# rolling_resistance.net
KiCad netlist of a schematic drawn in EAGLE
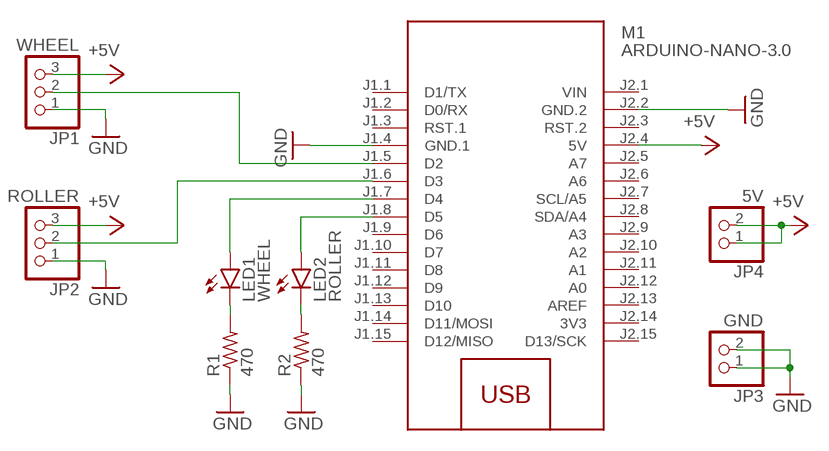
[diagram p0: schematic, sheet 1]

(export (version "E")
  (design (tool "Eeschema 10.0.6"))
  (components
    (comp (ref "JP1")
      (value "WHEEL")
      (footprint "eagle-import:1X03")
      (libsource (lib "eagle-import") (part "PINHD-1X3"))
    )
    (comp (ref "JP2")
      (value "ROLLER")
      (footprint "eagle-import:1X03")
      (libsource (lib "eagle-import") (part "PINHD-1X3"))
    )
    (comp (ref "JP3")
      (value "GND")
      (footprint "eagle-import:1X02")
      (libsource (lib "eagle-import") (part "PINHD-1X2"))
    )
    (comp (ref "JP4")
      (value "5V")
      (footprint "eagle-import:1X02")
      (libsource (lib "eagle-import") (part "PINHD-1X2"))
    )
    (comp (ref "LED1")
      (value "WHEEL")
      (footprint "eagle-import:SML0805")
      (libsource (lib "eagle-import") (part "LEDSML0805"))
    )
    (comp (ref "LED2")
      (value "ROLLER")
      (footprint "eagle-import:SML0805")
      (libsource (lib "eagle-import") (part "LEDSML0805"))
    )
    (comp (ref "M1")
      (value "ARDUINO-NANO-3.0")
      (footprint "eagle-import:ARDUINO-NANO-3.0")
      (libsource (lib "eagle-import") (part "ARDUINO-NANO-3.0"))
    )
    (comp (ref "R1")
      (value "470")
      (footprint "eagle-import:R0805")
      (libsource (lib "eagle-import") (part "R-US_R0805"))
    )
    (comp (ref "R2")
      (value "470")
      (footprint "eagle-import:R0805")
      (libsource (lib "eagle-import") (part "R-US_R0805"))
    )
  )
  (nets
    (net (code "1") (name "+5V") (class "Default")
      (node (ref "JP1") (pin "3") (pinfunction "3_3") (pintype "passive"))
      (node (ref "JP2") (pin "3") (pinfunction "3_3") (pintype "passive"))
      (node (ref "JP4") (pin "1") (pinfunction "1_1") (pintype "passive"))
      (node (ref "JP4") (pin "2") (pinfunction "2_2") (pintype "passive"))
      (node (ref "M1") (pin "J2.4") (pinfunction "5V_J2.4") (pintype "power_in"))
    )
    (net (code "2") (name "/3V3") (class "Default")
      (node (ref "M1") (pin "J2.14") (pinfunction "3V3_J2.14") (pintype "power_in"))
    )
    (net (code "3") (name "/VIN") (class "Default")
      (node (ref "M1") (pin "J2.1") (pinfunction "VIN_J2.1") (pintype "power_in"))
    )
    (net (code "4") (name "GND") (class "Default")
      (node (ref "JP1") (pin "1") (pinfunction "1_1") (pintype "passive"))
      (node (ref "JP2") (pin "1") (pinfunction "1_1") (pintype "passive"))
      (node (ref "JP3") (pin "1") (pinfunction "1_1") (pintype "passive"))
      (node (ref "JP3") (pin "2") (pinfunction "2_2") (pintype "passive"))
      (node (ref "M1") (pin "J1.4") (pinfunction "GND.1_J1.4") (pintype "power_in"))
      (node (ref "M1") (pin "J2.2") (pinfunction "GND.2_J2.2") (pintype "power_in"))
      (node (ref "R1") (pin "1") (pinfunction "1_1") (pintype "passive"))
      (node (ref "R2") (pin "1") (pinfunction "1_1") (pintype "passive"))
    )
    (net (code "5") (name "Net-(LED1-PadC)") (class "Default")
      (node (ref "LED1") (pin "C") (pinfunction "C_C") (pintype "passive"))
      (node (ref "R1") (pin "2") (pinfunction "2_2") (pintype "passive"))
    )
    (net (code "6") (name "Net-(LED2-PadC)") (class "Default")
      (node (ref "LED2") (pin "C") (pinfunction "C_C") (pintype "passive"))
      (node (ref "R2") (pin "2") (pinfunction "2_2") (pintype "passive"))
    )
    (net (code "7") (name "Net-(M1-D2)") (class "Default")
      (node (ref "JP1") (pin "2") (pinfunction "2_2") (pintype "passive"))
      (node (ref "M1") (pin "J1.5") (pinfunction "D2_J1.5") (pintype "bidirectional"))
    )
    (net (code "8") (name "Net-(M1-D3)") (class "Default")
      (node (ref "JP2") (pin "2") (pinfunction "2_2") (pintype "passive"))
      (node (ref "M1") (pin "J1.6") (pinfunction "D3_J1.6") (pintype "bidirectional"))
    )
    (net (code "9") (name "Net-(M1-D4)") (class "Default")
      (node (ref "LED1") (pin "A") (pinfunction "A_A") (pintype "passive"))
      (node (ref "M1") (pin "J1.7") (pinfunction "D4_J1.7") (pintype "bidirectional"))
    )
    (net (code "10") (name "Net-(M1-D5)") (class "Default")
      (node (ref "LED2") (pin "A") (pinfunction "A_A") (pintype "passive"))
      (node (ref "M1") (pin "J1.8") (pinfunction "D5_J1.8") (pintype "bidirectional"))
    )
    (net (code "11") (name "unconnected-(M1-A0-PadJ2.12)") (class "Default")
      (node (ref "M1") (pin "J2.12") (pinfunction "A0_J2.12") (pintype "bidirectional"))
    )
    (net (code "12") (name "unconnected-(M1-A1-PadJ2.11)") (class "Default")
      (node (ref "M1") (pin "J2.11") (pinfunction "A1_J2.11") (pintype "bidirectional"))
    )
    (net (code "13") (name "unconnected-(M1-A2-PadJ2.10)") (class "Default")
      (node (ref "M1") (pin "J2.10") (pinfunction "A2_J2.10") (pintype "bidirectional"))
    )
    (net (code "14") (name "unconnected-(M1-A3-PadJ2.9)") (class "Default")
      (node (ref "M1") (pin "J2.9") (pinfunction "A3_J2.9") (pintype "bidirectional"))
    )
    (net (code "15") (name "unconnected-(M1-A6-PadJ2.6)") (class "Default")
      (node (ref "M1") (pin "J2.6") (pinfunction "A6_J2.6") (pintype "bidirectional"))
    )
    (net (code "16") (name "unconnected-(M1-A7-PadJ2.5)") (class "Default")
      (node (ref "M1") (pin "J2.5") (pinfunction "A7_J2.5") (pintype "bidirectional"))
    )
    (net (code "17") (name "unconnected-(M1-AREF-PadJ2.13)") (class "Default")
      (node (ref "M1") (pin "J2.13") (pinfunction "AREF_J2.13") (pintype "bidirectional"))
    )
    (net (code "18") (name "unconnected-(M1-D0{slash}RX-PadJ1.2)") (class "Default")
      (node (ref "M1") (pin "J1.2") (pinfunction "D0/RX_J1.2") (pintype "bidirectional"))
    )
    (net (code "19") (name "unconnected-(M1-D1{slash}TX-PadJ1.1)") (class "Default")
      (node (ref "M1") (pin "J1.1") (pinfunction "D1/TX_J1.1") (pintype "bidirectional"))
    )
    (net (code "20") (name "unconnected-(M1-D6-PadJ1.9)") (class "Default")
      (node (ref "M1") (pin "J1.9") (pinfunction "D6_J1.9") (pintype "bidirectional"))
    )
    (net (code "21") (name "unconnected-(M1-D7-PadJ1.10)") (class "Default")
      (node (ref "M1") (pin "J1.10") (pinfunction "D7_J1.10") (pintype "bidirectional"))
    )
    (net (code "22") (name "unconnected-(M1-D8-PadJ1.11)") (class "Default")
      (node (ref "M1") (pin "J1.11") (pinfunction "D8_J1.11") (pintype "bidirectional"))
    )
    (net (code "23") (name "unconnected-(M1-D9-PadJ1.12)") (class "Default")
      (node (ref "M1") (pin "J1.12") (pinfunction "D9_J1.12") (pintype "bidirectional"))
    )
    (net (code "24") (name "unconnected-(M1-D10-PadJ1.13)") (class "Default")
      (node (ref "M1") (pin "J1.13") (pinfunction "D10_J1.13") (pintype "bidirectional"))
    )
    (net (code "25") (name "unconnected-(M1-D11{slash}MOSI-PadJ1.14)") (class "Default")
      (node (ref "M1") (pin "J1.14") (pinfunction "D11/MOSI_J1.14") (pintype "bidirectional"))
    )
    (net (code "26") (name "unconnected-(M1-D12{slash}MISO-PadJ1.15)") (class "Default")
      (node (ref "M1") (pin "J1.15") (pinfunction "D12/MISO_J1.15") (pintype "bidirectional"))
    )
    (net (code "27") (name "unconnected-(M1-D13{slash}SCK-PadJ2.15)") (class "Default")
      (node (ref "M1") (pin "J2.15") (pinfunction "D13/SCK_J2.15") (pintype "bidirectional"))
    )
    (net (code "28") (name "unconnected-(M1-RST.1-PadJ1.3)") (class "Default")
      (node (ref "M1") (pin "J1.3") (pinfunction "RST.1_J1.3") (pintype "bidirectional"))
    )
    (net (code "29") (name "unconnected-(M1-RST.2-PadJ2.3)") (class "Default")
      (node (ref "M1") (pin "J2.3") (pinfunction "RST.2_J2.3") (pintype "bidirectional"))
    )
    (net (code "30") (name "unconnected-(M1-SCL{slash}A5-PadJ2.7)") (class "Default")
      (node (ref "M1") (pin "J2.7") (pinfunction "SCL/A5_J2.7") (pintype "bidirectional"))
    )
    (net (code "31") (name "unconnected-(M1-SDA{slash}A4-PadJ2.8)") (class "Default")
      (node (ref "M1") (pin "J2.8") (pinfunction "SDA/A4_J2.8") (pintype "bidirectional"))
    )
  )
)
